# rpmsens.net
KiCad netlist of a schematic drawn in Altium Designer
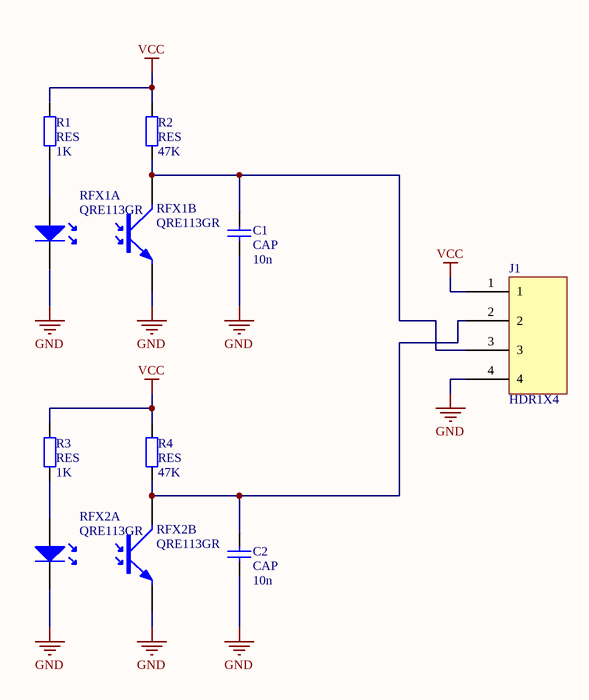
[diagram p0: rpmsens.SchDoc]

(export (version "E")
  (design (tool "Eeschema 10.0.6"))
  (components
    (comp (ref "C1")
      (value "CAP")
      (footprint "CAPC1608X08M")
      (description "Capacitor")
      (fields (field (name "ALTIUM_VALUE") "10n") (field (name "PUBLISHER") "Altium Limited"))
      (libsource (lib "std") (part "CAP"))
    )
    (comp (ref "C2")
      (value "CAP")
      (footprint "CAPC1608X08M")
      (description "Capacitor")
      (fields (field (name "ALTIUM_VALUE") "10n") (field (name "PUBLISHER") "Altium Limited"))
      (libsource (lib "std") (part "CAP"))
    )
    (comp (ref "J1")
      (value "HDR1X4")
      (footprint "HEADER_1X4")
      (description "4pin header")
      (libsource (lib "std") (part "HDR1X4"))
    )
    (comp (ref "R1")
      (value "RES")
      (footprint "RESC1608X06M")
      (description "Resistor")
      (fields (field (name "ALTIUM_VALUE") "1K") (field (name "PUBLISHER") "Altium Limited"))
      (libsource (lib "std") (part "RES"))
    )
    (comp (ref "R2")
      (value "RES")
      (footprint "RESC1608X06M")
      (description "Resistor")
      (fields (field (name "ALTIUM_VALUE") "47K") (field (name "PUBLISHER") "Altium Limited"))
      (libsource (lib "std") (part "RES"))
    )
    (comp (ref "R3")
      (value "RES")
      (footprint "RESC1608X06M")
      (description "Resistor")
      (fields (field (name "ALTIUM_VALUE") "1K") (field (name "PUBLISHER") "Altium Limited"))
      (libsource (lib "std") (part "RES"))
    )
    (comp (ref "R4")
      (value "RES")
      (footprint "RESC1608X06M")
      (description "Resistor")
      (fields (field (name "ALTIUM_VALUE") "47K") (field (name "PUBLISHER") "Altium Limited"))
      (libsource (lib "std") (part "RES"))
    )
    (comp (ref "RFX1")
      (value "QRE113GR")
      (footprint "RFX4")
      (description "SMT Reflective Object Sensor")
      (libsource (lib "std") (part "QRE113GR"))
    )
    (comp (ref "RFX2")
      (value "QRE113GR")
      (footprint "RFX4")
      (description "SMT Reflective Object Sensor")
      (libsource (lib "std") (part "QRE113GR"))
    )
  )
  (nets
    (net (code "1") (name "GND") (class "Default")
      (node (ref "C1") (pin "1") (pinfunction "1_1") (pintype "passive"))
      (node (ref "C2") (pin "1") (pinfunction "1_1") (pintype "passive"))
      (node (ref "J1") (pin "4") (pinfunction "4_4") (pintype "passive"))
      (node (ref "RFX1") (pin "2") (pinfunction "K_2") (pintype "passive"))
      (node (ref "RFX1") (pin "4") (pinfunction "E_4") (pintype "passive"))
      (node (ref "RFX2") (pin "2") (pinfunction "K_2") (pintype "passive"))
      (node (ref "RFX2") (pin "4") (pinfunction "E_4") (pintype "passive"))
    )
    (net (code "2") (name "Net-(RFX1A-A)") (class "Default")
      (node (ref "R1") (pin "1") (pinfunction "1_1") (pintype "passive"))
      (node (ref "RFX1") (pin "1") (pinfunction "A_1") (pintype "passive"))
    )
    (net (code "3") (name "Net-(RFX1B-C)") (class "Default")
      (node (ref "C1") (pin "2") (pinfunction "2_2") (pintype "passive"))
      (node (ref "J1") (pin "3") (pinfunction "3_3") (pintype "passive"))
      (node (ref "R2") (pin "1") (pinfunction "1_1") (pintype "passive"))
      (node (ref "RFX1") (pin "3") (pinfunction "C_3") (pintype "passive"))
    )
    (net (code "4") (name "Net-(RFX2A-A)") (class "Default")
      (node (ref "R3") (pin "1") (pinfunction "1_1") (pintype "passive"))
      (node (ref "RFX2") (pin "1") (pinfunction "A_1") (pintype "passive"))
    )
    (net (code "5") (name "Net-(RFX2B-C)") (class "Default")
      (node (ref "C2") (pin "2") (pinfunction "2_2") (pintype "passive"))
      (node (ref "J1") (pin "2") (pinfunction "2_2") (pintype "passive"))
      (node (ref "R4") (pin "1") (pinfunction "1_1") (pintype "passive"))
      (node (ref "RFX2") (pin "3") (pinfunction "C_3") (pintype "passive"))
    )
    (net (code "6") (name "VCC") (class "Default")
      (node (ref "J1") (pin "1") (pinfunction "1_1") (pintype "passive"))
      (node (ref "R1") (pin "2") (pinfunction "2_2") (pintype "passive"))
      (node (ref "R2") (pin "2") (pinfunction "2_2") (pintype "passive"))
      (node (ref "R3") (pin "2") (pinfunction "2_2") (pintype "passive"))
      (node (ref "R4") (pin "2") (pinfunction "2_2") (pintype "passive"))
    )
  )
)
